# CH32V407VET-R0.net
KiCad netlist of a schematic drawn in Altium Designer
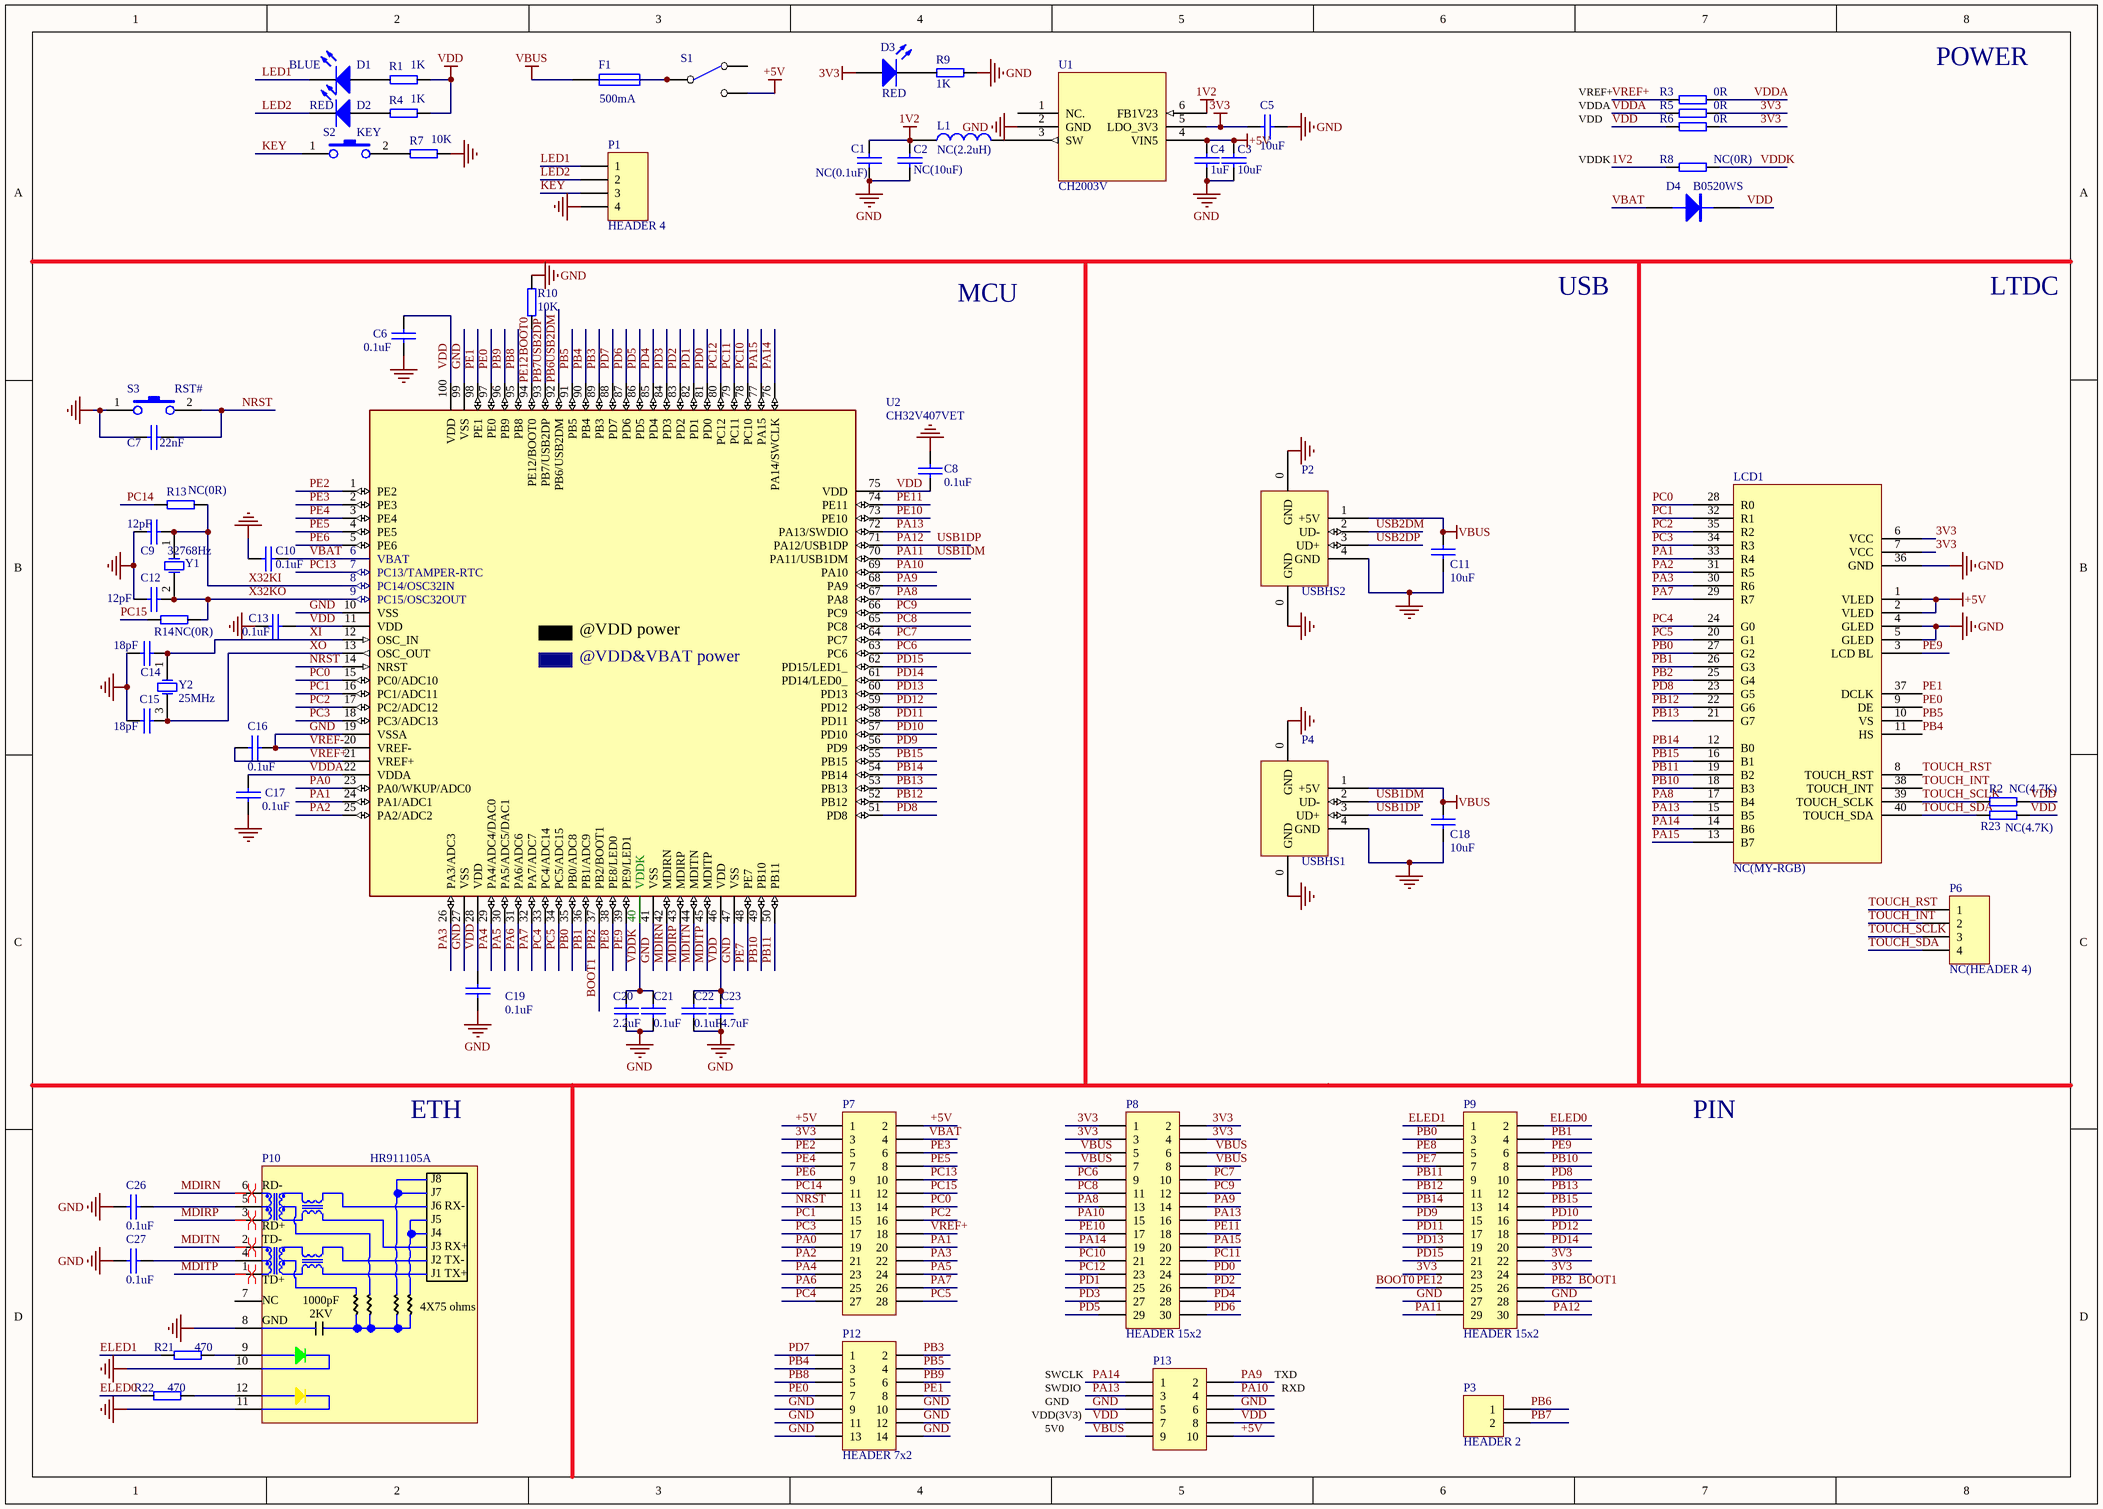
[diagram p0: CH32V407VET-R0.SchDoc]

(export (version "E")
  (design (tool "Eeschema 10.0.6"))
  (components
    (comp (ref "C1")
      (value "NC(0.1uF)")
      (footprint "0402_C")
      (description "Capacitor")
      (libsource (lib "") (part "CAP_2"))
    )
    (comp (ref "C2")
      (value "NC(10uF)")
      (footprint "0603_C")
      (description "Capacitor")
      (libsource (lib "*") (part "CAP"))
    )
    (comp (ref "C3")
      (value "10uF")
      (footprint "0603_C")
      (description "Capacitor")
      (libsource (lib "*") (part "CAP"))
    )
    (comp (ref "C4")
      (value "1uF")
      (footprint "0402_C")
      (description "Capacitor")
      (libsource (lib "") (part "CAP_2"))
    )
    (comp (ref "C5")
      (value "10uF")
      (footprint "0603_C")
      (description "Capacitor")
      (libsource (lib "*") (part "CAP"))
    )
    (comp (ref "C6")
      (value "0.1uF")
      (footprint "0402_C")
      (description "Capacitor")
      (libsource (lib "*") (part "CAP"))
    )
    (comp (ref "C7")
      (value "22nF")
      (footprint "0402_C")
      (description "Capacitor")
      (libsource (lib "") (part "CAP_1"))
    )
    (comp (ref "C8")
      (value "0.1uF")
      (footprint "0402_C")
      (description "Capacitor")
      (libsource (lib "*") (part "CAP"))
    )
    (comp (ref "C9")
      (value "12pF")
      (footprint "0402_C")
      (description "Capacitor")
      (libsource (lib "*") (part "CAP"))
    )
    (comp (ref "C10")
      (value "0.1uF")
      (footprint "0402_C")
      (description "Capacitor")
      (libsource (lib "*") (part "CAP"))
    )
    (comp (ref "C11")
      (value "10uF")
      (footprint "0603_C")
      (description "Capacitor")
      (libsource (lib "") (part "CAP_1"))
    )
    (comp (ref "C12")
      (value "12pF")
      (footprint "0402_C")
      (description "Capacitor")
      (libsource (lib "*") (part "CAP"))
    )
    (comp (ref "C13")
      (value "0.1uF")
      (footprint "0402_C")
      (description "Capacitor")
      (libsource (lib "*") (part "CAP"))
    )
    (comp (ref "C14")
      (value "18pF")
      (footprint "0402_C")
      (description "Capacitor")
      (libsource (lib "*") (part "CAP"))
    )
    (comp (ref "C15")
      (value "18pF")
      (footprint "0402_C")
      (description "Capacitor")
      (libsource (lib "*") (part "CAP"))
    )
    (comp (ref "C16")
      (value "0.1uF")
      (footprint "0402_C")
      (description "Capacitor")
      (libsource (lib "*") (part "CAP"))
    )
    (comp (ref "C17")
      (value "0.1uF")
      (footprint "0402_C")
      (description "Capacitor")
      (libsource (lib "*") (part "CAP"))
    )
    (comp (ref "C18")
      (value "10uF")
      (footprint "0603_C")
      (description "Capacitor")
      (libsource (lib "") (part "CAP_1"))
    )
    (comp (ref "C19")
      (value "0.1uF")
      (footprint "0402_C")
      (description "Capacitor")
      (libsource (lib "*") (part "CAP"))
    )
    (comp (ref "C20")
      (value "2.2uF")
      (footprint "0402_C")
      (description "Capacitor")
      (libsource (lib "*") (part "CAP"))
    )
    (comp (ref "C21")
      (value "0.1uF")
      (footprint "0402_C")
      (description "Capacitor")
      (libsource (lib "*") (part "CAP"))
    )
    (comp (ref "C22")
      (value "0.1uF")
      (footprint "0402_C")
      (description "Capacitor")
      (libsource (lib "*") (part "CAP"))
    )
    (comp (ref "C23")
      (value "4.7uF")
      (footprint "0402_C")
      (description "Capacitor")
      (libsource (lib "*") (part "CAP"))
    )
    (comp (ref "C26")
      (value "0.1uF")
      (footprint "0402_C")
      (description "Capacitor")
      (libsource (lib "wch_sch_others") (part "CAP"))
    )
    (comp (ref "C27")
      (value "0.1uF")
      (footprint "0402_C")
      (description "Capacitor")
      (libsource (lib "wch_sch_others") (part "CAP"))
    )
    (comp (ref "D1")
      (value "BLUE")
      (footprint "0603+")
      (description "Typical INFRARED GaAs LED")
      (fields (field (name "PUBLISHER") "Altium Limited"))
      (libsource (lib "*") (part "LED0"))
    )
    (comp (ref "D2")
      (value "RED")
      (footprint "0603+")
      (description "Typical INFRARED GaAs LED")
      (fields (field (name "PUBLISHER") "Altium Limited"))
      (libsource (lib "*") (part "LED0"))
    )
    (comp (ref "D3")
      (value "RED")
      (footprint "0603+")
      (description "Typical INFRARED GaAs LED")
      (fields (field (name "PUBLISHER") "Altium Limited"))
      (libsource (lib "*") (part "LED0"))
    )
    (comp (ref "D4")
      (value "B0520WS")
      (footprint "SOD-323")
      (description "Diode")
      (libsource (lib "*") (part "DIODE"))
    )
    (comp (ref "F1")
      (value "500mA")
      (footprint "0603")
      (description "Fuse")
      (libsource (lib "wch_sch_others") (part "FUSE1"))
    )
    (comp (ref "L1") (value "NC(2.2uH)") (footprint "CD32") (libsource (lib "*") (part "INDUCTOR")))
    (comp (ref "LCD1")
      (value "NC(MY-RGB)")
      (footprint "FPC40P-0.5-FK750M3")
      (libsource (lib "MY-显示") (part "MY-RGB"))
    )
    (comp (ref "P1")
      (value "HEADER 4")
      (footprint "SIP4-2.54mm")
      (description "Header, 4-Pin")
      (libsource (lib "wch_sch_others") (part "HEADER 4"))
    )
    (comp (ref "P2")
      (value "USBHS2")
      (footprint "USBAF")
      (description "USB Port")
      (libsource (lib "*") (part "USB"))
    )
    (comp (ref "P3")
      (value "HEADER 2")
      (footprint "MYPCB:SIP2-2.54mm")
      (description "Header, 2-Pin")
      (libsource (lib "wch_sch_others") (part "HEADER 2"))
    )
    (comp (ref "P4")
      (value "USBHS1")
      (footprint "USBAF")
      (description "USB Port")
      (libsource (lib "*") (part "USB"))
    )
    (comp (ref "P6")
      (value "NC(HEADER 4)")
      (footprint "SIP4-2.54mm")
      (description "Header, 4-Pin")
      (libsource (lib "wch_sch_others") (part "HEADER 4"))
    )
    (comp (ref "P7")
      (value "HEADER 14x2")
      (footprint "MYPCB:IDC28-2.54MM")
      (description "Header, 14-Pin, Dual row")
      (libsource (lib "wch_sch_others") (part "HEADER 14x2"))
    )
    (comp (ref "P8")
      (value "HEADER 15x2")
      (footprint "MYPCB:IDC30-2.54MM")
      (description "Header, 15-Pin, Dual row")
      (libsource (lib "wch_sch_others") (part "HEADER 15x2"))
    )
    (comp (ref "P9")
      (value "HEADER 15x2")
      (footprint "MYPCB:IDC30-2.54MM")
      (description "Header, 15-Pin, Dual row")
      (libsource (lib "wch_sch_others") (part "HEADER 15x2"))
    )
    (comp (ref "P10") (value "HR911105A") (footprint "HR911105A") (libsource (lib "*") (part "HR911105A")))
    (comp (ref "P12")
      (value "HEADER 7x2")
      (footprint "MYPCB:IDC14-2.54mm")
      (description "Header, 7-Pin, Dual row")
      (libsource (lib "wch_sch_others") (part "HEADER 7x2"))
    )
    (comp (ref "P13")
      (value "LINK")
      (footprint "IDC10-2.54mm")
      (description "Header, 5-Pin, Dual row, Right Angle")
      (fields (field (name "PUBLISHER") "Altium Limited"))
      (libsource (lib "Miscellaneous Connectors") (part "Header 5X2H"))
    )
    (comp (ref "R1") (value "1K") (footprint "0402") (libsource (lib "wch_sch_others") (part "RES")))
    (comp (ref "R2") (value "NC(4.7K)") (footprint "0402") (libsource (lib "wch_sch_others") (part "RES")))
    (comp (ref "R3") (value "0R") (footprint "0402") (libsource (lib "*") (part "R")))
    (comp (ref "R4") (value "1K") (footprint "0402") (libsource (lib "wch_sch_others") (part "RES")))
    (comp (ref "R5") (value "0R") (footprint "0402") (libsource (lib "*") (part "R")))
    (comp (ref "R6") (value "0R") (footprint "0402") (libsource (lib "*") (part "R")))
    (comp (ref "R7") (value "10K") (footprint "0402") (libsource (lib "wch_sch_others") (part "RES")))
    (comp (ref "R8") (value "NC(0R)") (footprint "0402") (libsource (lib "*") (part "R")))
    (comp (ref "R9") (value "1K") (footprint "0402") (libsource (lib "wch_sch_others") (part "RES")))
    (comp (ref "R10") (value "10K") (footprint "0402") (libsource (lib "wch_sch_others") (part "RES")))
    (comp (ref "R13") (value "NC(0R)") (footprint "0402") (libsource (lib "wch_sch_others") (part "RES")))
    (comp (ref "R14") (value "NC(0R)") (footprint "0402") (libsource (lib "wch_sch_others") (part "RES")))
    (comp (ref "R21") (value "470") (footprint "0402") (libsource (lib "wch_sch_others") (part "RES")))
    (comp (ref "R22") (value "470") (footprint "0402") (libsource (lib "wch_sch_others") (part "RES")))
    (comp (ref "R23") (value "NC(4.7K)") (footprint "0402") (libsource (lib "wch_sch_others") (part "RES")))
    (comp (ref "S1") (value "SW SPDT") (footprint "SW1") (libsource (lib "*") (part "SW SPDT")))
    (comp (ref "S2")
      (value "KEY")
      (footprint "SMD_6.1x3.65x2.5mm-KEY")
      (libsource (lib "wch_sch_others") (part "KEY1"))
    )
    (comp (ref "S3")
      (value "RST#")
      (footprint "SMD_6.1x3.65x2.5mm-KEY")
      (libsource (lib "wch_sch_others") (part "KEY1"))
    )
    (comp (ref "U1")
      (value "CH2003V")
      (footprint "SOT-23-6")
      (description "Step-Down DC-DC Converter, 5V input, 1.23V * 800mA output, with LDO 3.3V * 200mA")
      (libsource (lib "CHXXX") (part "CH2003V"))
    )
    (comp (ref "U2")
      (value "CH32V407VET")
      (footprint "LQFP100")
      (description "RISC-V FPU HD-MCU, 175MHz, USB_480M, 100M Ethernet & Phy, CAN, DVP, ADC, DAC")
      (libsource (lib "CHXXX") (part "CH32V407VET"))
    )
    (comp (ref "Y1")
      (value "32768Hz")
      (footprint "FC-135")
      (description "Crystal Oscillator")
      (fields (field (name "PUBLISHER") "Altium Limited"))
      (libsource (lib "*") (part "XTAL"))
    )
    (comp (ref "Y2")
      (value "25MHz")
      (footprint "XT3225")
      (description "Crystal Oscillator")
      (fields (field (name "PUBLISHER") "Altium Limited"))
      (libsource (lib "") (part "XTAL_1"))
    )
  )
  (nets
    (net (code "1") (name "+5V") (class "Default")
      (node (ref "C3") (pin "2") (pinfunction "2_2") (pintype "passive"))
      (node (ref "C4") (pin "2") (pinfunction "2_2") (pintype "passive"))
      (node (ref "LCD1") (pin "1") (pinfunction "VLED_1") (pintype "passive"))
      (node (ref "LCD1") (pin "2") (pinfunction "VLED_2") (pintype "passive"))
      (node (ref "P13") (pin "10") (pinfunction "10_10") (pintype "passive"))
      (node (ref "P7") (pin "1") (pinfunction "1_1") (pintype "passive"))
      (node (ref "P7") (pin "2") (pinfunction "2_2") (pintype "passive"))
      (node (ref "S1") (pin "2") (pinfunction "NC_2") (pintype "passive"))
      (node (ref "U1") (pin "4") (pinfunction "VIN5_4") (pintype "power_in"))
    )
    (net (code "3") (name "/BOOT0") (class "Default")
      (node (ref "P9") (pin "25") (pinfunction "25_25") (pintype "passive"))
      (node (ref "R10") (pin "2") (pintype "passive"))
      (node (ref "U2") (pin "94") (pinfunction "PE12/BOOT0_94") (pintype "bidirectional"))
    )
    (net (code "4") (name "/BOOT1") (class "Default")
      (node (ref "LCD1") (pin "25") (pinfunction "G4_25") (pintype "passive"))
      (node (ref "P9") (pin "26") (pinfunction "26_26") (pintype "passive"))
      (node (ref "U2") (pin "37") (pinfunction "PB2/BOOT1_37") (pintype "bidirectional"))
    )
    (net (code "5") (name "/ELED0") (class "Default")
      (node (ref "P9") (pin "2") (pinfunction "2_2") (pintype "passive"))
      (node (ref "R22") (pin "1") (pintype "passive"))
    )
    (net (code "6") (name "/ELED1") (class "Default")
      (node (ref "P9") (pin "1") (pinfunction "1_1") (pintype "passive"))
      (node (ref "R21") (pin "1") (pintype "passive"))
    )
    (net (code "7") (name "/KEY") (class "Default")
      (node (ref "P1") (pin "3") (pinfunction "3_3") (pintype "passive"))
      (node (ref "S2") (pin "1") (pinfunction "1_1") (pintype "passive"))
    )
    (net (code "8") (name "/LED1") (class "Default")
      (node (ref "D1") (pin "2") (pinfunction "K_2") (pintype "passive"))
      (node (ref "P1") (pin "1") (pinfunction "1_1") (pintype "passive"))
    )
    (net (code "9") (name "/LED2") (class "Default")
      (node (ref "D2") (pin "2") (pinfunction "K_2") (pintype "passive"))
      (node (ref "P1") (pin "2") (pinfunction "2_2") (pintype "passive"))
    )
    (net (code "10") (name "/MDIRN") (class "Default")
      (node (ref "P10") (pin "6") (pintype "passive"))
      (node (ref "U2") (pin "42") (pinfunction "MDIRN_42") (pintype "bidirectional"))
    )
    (net (code "11") (name "/MDIRP") (class "Default")
      (node (ref "P10") (pin "3") (pintype "passive"))
      (node (ref "U2") (pin "43") (pinfunction "MDIRP_43") (pintype "bidirectional"))
    )
    (net (code "12") (name "/MDITN") (class "Default")
      (node (ref "P10") (pin "2") (pintype "passive"))
      (node (ref "U2") (pin "44") (pinfunction "MDITN_44") (pintype "bidirectional"))
    )
    (net (code "13") (name "/MDITP") (class "Default")
      (node (ref "P10") (pin "1") (pintype "passive"))
      (node (ref "U2") (pin "45") (pinfunction "MDITP_45") (pintype "bidirectional"))
    )
    (net (code "14") (name "/NRST") (class "Default")
      (node (ref "C7") (pin "2") (pinfunction "2_2") (pintype "passive"))
      (node (ref "P7") (pin "13") (pinfunction "13_13") (pintype "passive"))
      (node (ref "S3") (pin "2") (pinfunction "2_2") (pintype "passive"))
      (node (ref "U2") (pin "14") (pinfunction "NRST_14") (pintype "input"))
    )
    (net (code "15") (name "/PA0") (class "Default")
      (node (ref "P7") (pin "19") (pinfunction "19_19") (pintype "passive"))
      (node (ref "U2") (pin "23") (pinfunction "PA0/WKUP/ADC0_23") (pintype "bidirectional"))
    )
    (net (code "16") (name "/PA1") (class "Default")
      (node (ref "LCD1") (pin "33") (pinfunction "R4_33") (pintype "passive"))
      (node (ref "P7") (pin "20") (pinfunction "20_20") (pintype "passive"))
      (node (ref "U2") (pin "24") (pinfunction "PA1/ADC1_24") (pintype "bidirectional"))
    )
    (net (code "17") (name "/PA2") (class "Default")
      (node (ref "LCD1") (pin "31") (pinfunction "R5_31") (pintype "passive"))
      (node (ref "P7") (pin "21") (pinfunction "21_21") (pintype "passive"))
      (node (ref "U2") (pin "25") (pinfunction "PA2/ADC2_25") (pintype "bidirectional"))
    )
    (net (code "18") (name "/PA3") (class "Default")
      (node (ref "LCD1") (pin "30") (pinfunction "R6_30") (pintype "passive"))
      (node (ref "P7") (pin "22") (pinfunction "22_22") (pintype "passive"))
      (node (ref "U2") (pin "26") (pinfunction "PA3/ADC3_26") (pintype "bidirectional"))
    )
    (net (code "19") (name "/PA4") (class "Default")
      (node (ref "P7") (pin "23") (pinfunction "23_23") (pintype "passive"))
      (node (ref "U2") (pin "29") (pinfunction "PA4/ADC4/DAC0_29") (pintype "bidirectional"))
    )
    (net (code "20") (name "/PA5") (class "Default")
      (node (ref "P7") (pin "24") (pinfunction "24_24") (pintype "passive"))
      (node (ref "U2") (pin "30") (pinfunction "PA5/ADC5/DAC1_30") (pintype "bidirectional"))
    )
    (net (code "21") (name "/PA6") (class "Default")
      (node (ref "P7") (pin "25") (pinfunction "25_25") (pintype "passive"))
      (node (ref "U2") (pin "31") (pinfunction "PA6/ADC6_31") (pintype "bidirectional"))
    )
    (net (code "22") (name "/PA7") (class "Default")
      (node (ref "LCD1") (pin "29") (pinfunction "R7_29") (pintype "passive"))
      (node (ref "P7") (pin "26") (pinfunction "26_26") (pintype "passive"))
      (node (ref "U2") (pin "32") (pinfunction "PA7/ADC7_32") (pintype "bidirectional"))
    )
    (net (code "23") (name "/PA8") (class "Default")
      (node (ref "LCD1") (pin "17") (pinfunction "B4_17") (pintype "passive"))
      (node (ref "P8") (pin "13") (pinfunction "13_13") (pintype "passive"))
      (node (ref "U2") (pin "67") (pinfunction "PA8_67") (pintype "bidirectional"))
    )
    (net (code "24") (name "/PA9") (class "Default")
      (node (ref "P13") (pin "2") (pinfunction "2_2") (pintype "passive"))
      (node (ref "P8") (pin "14") (pinfunction "14_14") (pintype "passive"))
      (node (ref "U2") (pin "68") (pinfunction "PA9_68") (pintype "bidirectional"))
    )
    (net (code "25") (name "/PA10") (class "Default")
      (node (ref "P13") (pin "4") (pinfunction "4_4") (pintype "passive"))
      (node (ref "P8") (pin "15") (pinfunction "15_15") (pintype "passive"))
      (node (ref "U2") (pin "69") (pinfunction "PA10_69") (pintype "bidirectional"))
    )
    (net (code "26") (name "/PA11") (class "Default")
      (node (ref "P4") (pin "2") (pinfunction "UD-_2") (pintype "bidirectional"))
      (node (ref "P9") (pin "29") (pinfunction "29_29") (pintype "passive"))
      (node (ref "U2") (pin "70") (pinfunction "PA11/USB1DM_70") (pintype "bidirectional"))
    )
    (net (code "27") (name "/PA12") (class "Default")
      (node (ref "P4") (pin "3") (pinfunction "UD+_3") (pintype "bidirectional"))
      (node (ref "P9") (pin "30") (pinfunction "30_30") (pintype "passive"))
      (node (ref "U2") (pin "71") (pinfunction "PA12/USB1DP_71") (pintype "bidirectional"))
    )
    (net (code "28") (name "/PA13") (class "Default")
      (node (ref "LCD1") (pin "15") (pinfunction "B5_15") (pintype "passive"))
      (node (ref "P13") (pin "3") (pinfunction "3_3") (pintype "passive"))
      (node (ref "P8") (pin "16") (pinfunction "16_16") (pintype "passive"))
      (node (ref "U2") (pin "72") (pinfunction "PA13/SWDIO_72") (pintype "bidirectional"))
    )
    (net (code "29") (name "/PA14") (class "Default")
      (node (ref "LCD1") (pin "14") (pinfunction "B6_14") (pintype "passive"))
      (node (ref "P13") (pin "1") (pinfunction "1_1") (pintype "passive"))
      (node (ref "P8") (pin "19") (pinfunction "19_19") (pintype "passive"))
      (node (ref "U2") (pin "76") (pinfunction "PA14/SWCLK_76") (pintype "bidirectional"))
    )
    (net (code "30") (name "/PA15") (class "Default")
      (node (ref "LCD1") (pin "13") (pinfunction "B7_13") (pintype "passive"))
      (node (ref "P8") (pin "20") (pinfunction "20_20") (pintype "passive"))
      (node (ref "U2") (pin "77") (pinfunction "PA15_77") (pintype "bidirectional"))
    )
    (net (code "31") (name "/PB0") (class "Default")
      (node (ref "LCD1") (pin "27") (pinfunction "G2_27") (pintype "passive"))
      (node (ref "P9") (pin "3") (pinfunction "3_3") (pintype "passive"))
      (node (ref "U2") (pin "35") (pinfunction "PB0/ADC8_35") (pintype "bidirectional"))
    )
    (net (code "32") (name "/PB1") (class "Default")
      (node (ref "LCD1") (pin "26") (pinfunction "G3_26") (pintype "passive"))
      (node (ref "P9") (pin "4") (pinfunction "4_4") (pintype "passive"))
      (node (ref "U2") (pin "36") (pinfunction "PB1/ADC9_36") (pintype "bidirectional"))
    )
    (net (code "33") (name "/PB3") (class "Default")
      (node (ref "P12") (pin "2") (pinfunction "2_2") (pintype "passive"))
      (node (ref "U2") (pin "89") (pinfunction "PB3_89") (pintype "bidirectional"))
    )
    (net (code "34") (name "/PB4") (class "Default")
      (node (ref "LCD1") (pin "11") (pinfunction "HS_11") (pintype "passive"))
      (node (ref "P12") (pin "3") (pinfunction "3_3") (pintype "passive"))
      (node (ref "U2") (pin "90") (pinfunction "PB4_90") (pintype "bidirectional"))
    )
    (net (code "35") (name "/PB5") (class "Default")
      (node (ref "LCD1") (pin "10") (pinfunction "VS_10") (pintype "passive"))
      (node (ref "P12") (pin "4") (pinfunction "4_4") (pintype "passive"))
      (node (ref "U2") (pin "91") (pinfunction "PB5_91") (pintype "bidirectional"))
    )
    (net (code "36") (name "/PB6") (class "Default")
      (node (ref "P2") (pin "2") (pinfunction "UD-_2") (pintype "bidirectional"))
      (node (ref "P3") (pin "1") (pinfunction "1_1") (pintype "passive"))
      (node (ref "U2") (pin "92") (pinfunction "PB6/USB2DM_92") (pintype "bidirectional"))
    )
    (net (code "37") (name "/PB7") (class "Default")
      (node (ref "P2") (pin "3") (pinfunction "UD+_3") (pintype "bidirectional"))
      (node (ref "P3") (pin "2") (pinfunction "2_2") (pintype "passive"))
      (node (ref "U2") (pin "93") (pinfunction "PB7/USB2DP_93") (pintype "bidirectional"))
    )
    (net (code "38") (name "/PB8") (class "Default")
      (node (ref "P12") (pin "5") (pinfunction "5_5") (pintype "passive"))
      (node (ref "U2") (pin "95") (pinfunction "PB8_95") (pintype "bidirectional"))
    )
    (net (code "39") (name "/PB9") (class "Default")
      (node (ref "P12") (pin "6") (pinfunction "6_6") (pintype "passive"))
      (node (ref "U2") (pin "96") (pinfunction "PB9_96") (pintype "bidirectional"))
    )
    (net (code "40") (name "/PB10") (class "Default")
      (node (ref "LCD1") (pin "18") (pinfunction "B3_18") (pintype "passive"))
      (node (ref "P9") (pin "8") (pinfunction "8_8") (pintype "passive"))
      (node (ref "U2") (pin "49") (pinfunction "PB10_49") (pintype "bidirectional"))
    )
    (net (code "41") (name "/PB11") (class "Default")
      (node (ref "LCD1") (pin "19") (pinfunction "B2_19") (pintype "passive"))
      (node (ref "P9") (pin "9") (pinfunction "9_9") (pintype "passive"))
      (node (ref "U2") (pin "50") (pinfunction "PB11_50") (pintype "bidirectional"))
    )
    (net (code "42") (name "/PB12") (class "Default")
      (node (ref "LCD1") (pin "22") (pinfunction "G6_22") (pintype "passive"))
      (node (ref "P9") (pin "11") (pinfunction "11_11") (pintype "passive"))
      (node (ref "U2") (pin "52") (pinfunction "PB12_52") (pintype "bidirectional"))
    )
    (net (code "43") (name "/PB13") (class "Default")
      (node (ref "LCD1") (pin "21") (pinfunction "G7_21") (pintype "passive"))
      (node (ref "P9") (pin "12") (pinfunction "12_12") (pintype "passive"))
      (node (ref "U2") (pin "53") (pinfunction "PB13_53") (pintype "bidirectional"))
    )
    (net (code "44") (name "/PB14") (class "Default")
      (node (ref "LCD1") (pin "12") (pinfunction "B0_12") (pintype "passive"))
      (node (ref "P9") (pin "13") (pinfunction "13_13") (pintype "passive"))
      (node (ref "U2") (pin "54") (pinfunction "PB14_54") (pintype "bidirectional"))
    )
    (net (code "45") (name "/PB15") (class "Default")
      (node (ref "LCD1") (pin "16") (pinfunction "B1_16") (pintype "passive"))
      (node (ref "P9") (pin "14") (pinfunction "14_14") (pintype "passive"))
      (node (ref "U2") (pin "55") (pinfunction "PB15_55") (pintype "bidirectional"))
    )
    (net (code "46") (name "/PC0") (class "Default")
      (node (ref "LCD1") (pin "28") (pinfunction "R0_28") (pintype "passive"))
      (node (ref "P7") (pin "14") (pinfunction "14_14") (pintype "passive"))
      (node (ref "U2") (pin "15") (pinfunction "PC0/ADC10_15") (pintype "bidirectional"))
    )
    (net (code "47") (name "/PC1") (class "Default")
      (node (ref "LCD1") (pin "32") (pinfunction "R1_32") (pintype "passive"))
      (node (ref "P7") (pin "15") (pinfunction "15_15") (pintype "passive"))
      (node (ref "U2") (pin "16") (pinfunction "PC1/ADC11_16") (pintype "bidirectional"))
    )
    (net (code "48") (name "/PC2") (class "Default")
      (node (ref "LCD1") (pin "35") (pinfunction "R2_35") (pintype "passive"))
      (node (ref "P7") (pin "16") (pinfunction "16_16") (pintype "passive"))
      (node (ref "U2") (pin "17") (pinfunction "PC2/ADC12_17") (pintype "bidirectional"))
    )
    (net (code "49") (name "/PC3") (class "Default")
      (node (ref "LCD1") (pin "34") (pinfunction "R3_34") (pintype "passive"))
      (node (ref "P7") (pin "17") (pinfunction "17_17") (pintype "passive"))
      (node (ref "U2") (pin "18") (pinfunction "PC3/ADC13_18") (pintype "bidirectional"))
    )
    (net (code "50") (name "/PC4") (class "Default")
      (node (ref "LCD1") (pin "24") (pinfunction "G0_24") (pintype "passive"))
      (node (ref "P7") (pin "27") (pinfunction "27_27") (pintype "passive"))
      (node (ref "U2") (pin "33") (pinfunction "PC4/ADC14_33") (pintype "bidirectional"))
    )
    (net (code "51") (name "/PC5") (class "Default")
      (node (ref "LCD1") (pin "20") (pinfunction "G1_20") (pintype "passive"))
      (node (ref "P7") (pin "28") (pinfunction "28_28") (pintype "passive"))
      (node (ref "U2") (pin "34") (pinfunction "PC5/ADC15_34") (pintype "bidirectional"))
    )
    (net (code "52") (name "/PC6") (class "Default")
      (node (ref "P8") (pin "9") (pinfunction "9_9") (pintype "passive"))
      (node (ref "U2") (pin "63") (pinfunction "PC6_63") (pintype "bidirectional"))
    )
    (net (code "53") (name "/PC7") (class "Default")
      (node (ref "P8") (pin "10") (pinfunction "10_10") (pintype "passive"))
      (node (ref "U2") (pin "64") (pinfunction "PC7_64") (pintype "bidirectional"))
    )
    (net (code "54") (name "/PC8") (class "Default")
      (node (ref "P8") (pin "11") (pinfunction "11_11") (pintype "passive"))
      (node (ref "U2") (pin "65") (pinfunction "PC8_65") (pintype "bidirectional"))
    )
    (net (code "55") (name "/PC9") (class "Default")
      (node (ref "P8") (pin "12") (pinfunction "12_12") (pintype "passive"))
      (node (ref "U2") (pin "66") (pinfunction "PC9_66") (pintype "bidirectional"))
    )
    (net (code "56") (name "/PC10") (class "Default")
      (node (ref "P8") (pin "21") (pinfunction "21_21") (pintype "passive"))
      (node (ref "U2") (pin "78") (pinfunction "PC10_78") (pintype "bidirectional"))
    )
    (net (code "57") (name "/PC11") (class "Default")
      (node (ref "P8") (pin "22") (pinfunction "22_22") (pintype "passive"))
      (node (ref "U2") (pin "79") (pinfunction "PC11_79") (pintype "bidirectional"))
    )
    (net (code "58") (name "/PC12") (class "Default")
      (node (ref "P8") (pin "23") (pinfunction "23_23") (pintype "passive"))
      (node (ref "U2") (pin "80") (pinfunction "PC12_80") (pintype "bidirectional"))
    )
    (net (code "59") (name "/PC13") (class "Default")
      (node (ref "P7") (pin "10") (pinfunction "10_10") (pintype "passive"))
      (node (ref "U2") (pin "7") (pinfunction "PC13/TAMPER-RTC_7") (pintype "bidirectional"))
    )
    (net (code "60") (name "/PC14") (class "Default")
      (node (ref "P7") (pin "11") (pinfunction "11_11") (pintype "passive"))
      (node (ref "R13") (pin "1") (pintype "passive"))
    )
    (net (code "61") (name "/PC15") (class "Default")
      (node (ref "P7") (pin "12") (pinfunction "12_12") (pintype "passive"))
      (node (ref "R14") (pin "1") (pintype "passive"))
    )
    (net (code "62") (name "/PD0") (class "Default")
      (node (ref "P8") (pin "24") (pinfunction "24_24") (pintype "passive"))
      (node (ref "U2") (pin "81") (pinfunction "PD0_81") (pintype "bidirectional"))
    )
    (net (code "63") (name "/PD1") (class "Default")
      (node (ref "P8") (pin "25") (pinfunction "25_25") (pintype "passive"))
      (node (ref "U2") (pin "82") (pinfunction "PD1_82") (pintype "bidirectional"))
    )
    (net (code "64") (name "/PD2") (class "Default")
      (node (ref "P8") (pin "26") (pinfunction "26_26") (pintype "passive"))
      (node (ref "U2") (pin "83") (pinfunction "PD2_83") (pintype "bidirectional"))
    )
    (net (code "65") (name "/PD3") (class "Default")
      (node (ref "P8") (pin "27") (pinfunction "27_27") (pintype "passive"))
      (node (ref "U2") (pin "84") (pinfunction "PD3_84") (pintype "bidirectional"))
    )
    (net (code "66") (name "/PD4") (class "Default")
      (node (ref "P8") (pin "28") (pinfunction "28_28") (pintype "passive"))
      (node (ref "U2") (pin "85") (pinfunction "PD4_85") (pintype "bidirectional"))
    )
    (net (code "67") (name "/PD5") (class "Default")
      (node (ref "P8") (pin "29") (pinfunction "29_29") (pintype "passive"))
      (node (ref "U2") (pin "86") (pinfunction "PD5_86") (pintype "bidirectional"))
    )
    (net (code "68") (name "/PD6") (class "Default")
      (node (ref "P8") (pin "30") (pinfunction "30_30") (pintype "passive"))
      (node (ref "U2") (pin "87") (pinfunction "PD6_87") (pintype "bidirectional"))
    )
    (net (code "69") (name "/PD7") (class "Default")
      (node (ref "P12") (pin "1") (pinfunction "1_1") (pintype "passive"))
      (node (ref "U2") (pin "88") (pinfunction "PD7_88") (pintype "bidirectional"))
    )
    (net (code "70") (name "/PD8") (class "Default")
      (node (ref "LCD1") (pin "23") (pinfunction "G5_23") (pintype "passive"))
      (node (ref "P9") (pin "10") (pinfunction "10_10") (pintype "passive"))
      (node (ref "U2") (pin "51") (pinfunction "PD8_51") (pintype "bidirectional"))
    )
    (net (code "71") (name "/PD9") (class "Default")
      (node (ref "P9") (pin "15") (pinfunction "15_15") (pintype "passive"))
      (node (ref "U2") (pin "56") (pinfunction "PD9_56") (pintype "bidirectional"))
    )
    (net (code "72") (name "/PD10") (class "Default")
      (node (ref "P9") (pin "16") (pinfunction "16_16") (pintype "passive"))
      (node (ref "U2") (pin "57") (pinfunction "PD10_57") (pintype "bidirectional"))
    )
    (net (code "73") (name "/PD11") (class "Default")
      (node (ref "P9") (pin "17") (pinfunction "17_17") (pintype "passive"))
      (node (ref "U2") (pin "58") (pinfunction "PD11_58") (pintype "bidirectional"))
    )
    (net (code "74") (name "/PD12") (class "Default")
      (node (ref "P9") (pin "18") (pinfunction "18_18") (pintype "passive"))
      (node (ref "U2") (pin "59") (pinfunction "PD12_59") (pintype "bidirectional"))
    )
    (net (code "75") (name "/PD13") (class "Default")
      (node (ref "P9") (pin "19") (pinfunction "19_19") (pintype "passive"))
      (node (ref "U2") (pin "60") (pinfunction "PD13_60") (pintype "bidirectional"))
    )
    (net (code "76") (name "/PD14") (class "Default")
      (node (ref "P9") (pin "20") (pinfunction "20_20") (pintype "passive"))
      (node (ref "U2") (pin "61") (pinfunction "PD14/LED0__61") (pintype "bidirectional"))
    )
    (net (code "77") (name "/PD15") (class "Default")
      (node (ref "P9") (pin "21") (pinfunction "21_21") (pintype "passive"))
      (node (ref "U2") (pin "62") (pinfunction "PD15/LED1__62") (pintype "bidirectional"))
    )
    (net (code "78") (name "/PE0") (class "Default")
      (node (ref "LCD1") (pin "9") (pinfunction "DE_9") (pintype "passive"))
      (node (ref "P12") (pin "7") (pinfunction "7_7") (pintype "passive"))
      (node (ref "U2") (pin "97") (pinfunction "PE0_97") (pintype "bidirectional"))
    )
    (net (code "79") (name "/PE1") (class "Default")
      (node (ref "LCD1") (pin "37") (pinfunction "DCLK_37") (pintype "passive"))
      (node (ref "P12") (pin "8") (pinfunction "8_8") (pintype "passive"))
      (node (ref "U2") (pin "98") (pinfunction "PE1_98") (pintype "bidirectional"))
    )
    (net (code "80") (name "/PE2") (class "Default")
      (node (ref "P7") (pin "5") (pinfunction "5_5") (pintype "passive"))
      (node (ref "U2") (pin "1") (pinfunction "PE2_1") (pintype "bidirectional"))
    )
    (net (code "81") (name "/PE3") (class "Default")
      (node (ref "P7") (pin "6") (pinfunction "6_6") (pintype "passive"))
      (node (ref "U2") (pin "2") (pinfunction "PE3_2") (pintype "bidirectional"))
    )
    (net (code "82") (name "/PE4") (class "Default")
      (node (ref "P7") (pin "7") (pinfunction "7_7") (pintype "passive"))
      (node (ref "U2") (pin "3") (pinfunction "PE4_3") (pintype "bidirectional"))
    )
    (net (code "83") (name "/PE5") (class "Default")
      (node (ref "P7") (pin "8") (pinfunction "8_8") (pintype "passive"))
      (node (ref "U2") (pin "4") (pinfunction "PE5_4") (pintype "bidirectional"))
    )
    (net (code "84") (name "/PE6") (class "Default")
      (node (ref "P7") (pin "9") (pinfunction "9_9") (pintype "passive"))
      (node (ref "U2") (pin "5") (pinfunction "PE6_5") (pintype "bidirectional"))
    )
    (net (code "85") (name "/PE7") (class "Default")
      (node (ref "P9") (pin "7") (pinfunction "7_7") (pintype "passive"))
      (node (ref "U2") (pin "48") (pinfunction "PE7_48") (pintype "bidirectional"))
    )
    (net (code "86") (name "/PE8") (class "Default")
      (node (ref "P9") (pin "5") (pinfunction "5_5") (pintype "passive"))
      (node (ref "U2") (pin "38") (pinfunction "PE8/LED0_38") (pintype "bidirectional"))
    )
    (net (code "87") (name "/PE9") (class "Default")
      (node (ref "LCD1") (pin "3") (pinfunction "LCD_BL_3") (pintype "passive"))
      (node (ref "P9") (pin "6") (pinfunction "6_6") (pintype "passive"))
      (node (ref "U2") (pin "39") (pinfunction "PE9/LED1_39") (pintype "bidirectional"))
    )
    (net (code "88") (name "/PE10") (class "Default")
      (node (ref "P8") (pin "17") (pinfunction "17_17") (pintype "passive"))
      (node (ref "U2") (pin "73") (pinfunction "PE10_73") (pintype "bidirectional"))
    )
    (net (code "89") (name "/PE11") (class "Default")
      (node (ref "P8") (pin "18") (pinfunction "18_18") (pintype "passive"))
      (node (ref "U2") (pin "74") (pinfunction "PE11_74") (pintype "bidirectional"))
    )
    (net (code "90") (name "/TOUCH_INT") (class "Default")
      (node (ref "LCD1") (pin "38") (pinfunction "TOUCH_INT_38") (pintype "passive"))
      (node (ref "P6") (pin "2") (pinfunction "2_2") (pintype "passive"))
    )
    (net (code "91") (name "/TOUCH_RST") (class "Default")
      (node (ref "LCD1") (pin "8") (pinfunction "TOUCH_RST_8") (pintype "passive"))
      (node (ref "P6") (pin "1") (pinfunction "1_1") (pintype "passive"))
    )
    (net (code "92") (name "/TOUCH_SCLK") (class "Default")
      (node (ref "LCD1") (pin "39") (pinfunction "TOUCH_SCLK_39") (pintype "passive"))
      (node (ref "P6") (pin "3") (pinfunction "3_3") (pintype "passive"))
      (node (ref "R2") (pin "2") (pintype "passive"))
    )
    (net (code "93") (name "/TOUCH_SDA") (class "Default")
      (node (ref "LCD1") (pin "40") (pinfunction "TOUCH_SDA_40") (pintype "passive"))
      (node (ref "P6") (pin "4") (pinfunction "4_4") (pintype "passive"))
      (node (ref "R23") (pin "2") (pintype "passive"))
    )
    (net (code "94") (name "/VBAT") (class "Default")
      (node (ref "C10") (pin "2") (pinfunction "2_2") (pintype "passive"))
      (node (ref "D4") (pin "1") (pinfunction "A_1") (pintype "passive"))
      (node (ref "P7") (pin "4") (pinfunction "4_4") (pintype "passive"))
      (node (ref "U2") (pin "6") (pinfunction "VBAT_6") (pintype "power_in"))
    )
    (net (code "95") (name "/VDDA") (class "Default")
      (node (ref "C17") (pin "1") (pinfunction "1_1") (pintype "passive"))
      (node (ref "R3") (pin "1") (pinfunction "1_1") (pintype "passive"))
      (node (ref "R5") (pin "2") (pinfunction "2_2") (pintype "passive"))
      (node (ref "U2") (pin "22") (pinfunction "VDDA_22") (pintype "power_in"))
    )
    (net (code "96") (name "/VDDK") (class "Default")
      (node (ref "C20") (pin "2") (pinfunction "2_2") (pintype "passive"))
      (node (ref "C21") (pin "2") (pinfunction "2_2") (pintype "passive"))
      (node (ref "R8") (pin "1") (pinfunction "1_1") (pintype "passive"))
      (node (ref "U2") (pin "40") (pinfunction "VDDK_40") (pintype "power_in"))
    )
    (net (code "97") (name "/VREF+") (class "Default")
      (node (ref "C16") (pin "1") (pinfunction "1_1") (pintype "passive"))
      (node (ref "P7") (pin "18") (pinfunction "18_18") (pintype "passive"))
      (node (ref "R3") (pin "2") (pinfunction "2_2") (pintype "passive"))
      (node (ref "U2") (pin "21") (pinfunction "VREF+_21") (pintype "power_in"))
    )
    (net (code "98") (name "/X32KI") (class "Default")
      (node (ref "C9") (pin "2") (pinfunction "2_2") (pintype "passive"))
      (node (ref "R13") (pin "2") (pintype "passive"))
      (node (ref "U2") (pin "8") (pinfunction "PC14/OSC32IN_8") (pintype "bidirectional"))
      (node (ref "Y1") (pin "1") (pinfunction "OSC1_1") (pintype "passive"))
    )
    (net (code "99") (name "/X32KO") (class "Default")
      (node (ref "C12") (pin "2") (pinfunction "2_2") (pintype "passive"))
      (node (ref "R14") (pin "2") (pintype "passive"))
      (node (ref "U2") (pin "9") (pinfunction "PC15/OSC32OUT_9") (pintype "bidirectional"))
      (node (ref "Y1") (pin "2") (pinfunction "OSC2_2") (pintype "passive"))
    )
    (net (code "100") (name "/XI") (class "Default")
      (node (ref "C14") (pin "2") (pinfunction "2_2") (pintype "passive"))
      (node (ref "U2") (pin "12") (pinfunction "OSC_IN_12") (pintype "input"))
      (node (ref "Y2") (pin "1") (pinfunction "OSC1_1") (pintype "passive"))
    )
    (net (code "101") (name "/XO") (class "Default")
      (node (ref "C15") (pin "2") (pinfunction "2_2") (pintype "passive"))
      (node (ref "U2") (pin "13") (pinfunction "OSC_OUT_13") (pintype "output"))
      (node (ref "Y2") (pin "3") (pinfunction "OSC2_3") (pintype "passive"))
    )
    (net (code "102") (name "1V2") (class "Default")
      (node (ref "C1") (pin "2") (pinfunction "2_2") (pintype "passive"))
      (node (ref "C2") (pin "2") (pinfunction "2_2") (pintype "passive"))
      (node (ref "L1") (pin "2") (pinfunction "2_2") (pintype "passive"))
      (node (ref "R8") (pin "2") (pinfunction "2_2") (pintype "passive"))
      (node (ref "U1") (pin "6") (pinfunction "FB1V23_6") (pintype "input"))
    )
    (net (code "103") (name "3V3") (class "Default")
      (node (ref "C5") (pin "2") (pinfunction "2_2") (pintype "passive"))
      (node (ref "D3") (pin "1") (pinfunction "A_1") (pintype "passive"))
      (node (ref "LCD1") (pin "6") (pinfunction "VCC_6") (pintype "passive"))
      (node (ref "LCD1") (pin "7") (pinfunction "VCC_7") (pintype "passive"))
      (node (ref "P7") (pin "3") (pinfunction "3_3") (pintype "passive"))
      (node (ref "P8") (pin "1") (pinfunction "1_1") (pintype "passive"))
      (node (ref "P8") (pin "2") (pinfunction "2_2") (pintype "passive"))
      (node (ref "P8") (pin "3") (pinfunction "3_3") (pintype "passive"))
      (node (ref "P8") (pin "4") (pinfunction "4_4") (pintype "passive"))
      (node (ref "P9") (pin "22") (pinfunction "22_22") (pintype "passive"))
      (node (ref "P9") (pin "23") (pinfunction "23_23") (pintype "passive"))
      (node (ref "P9") (pin "24") (pinfunction "24_24") (pintype "passive"))
      (node (ref "R5") (pin "1") (pinfunction "1_1") (pintype "passive"))
      (node (ref "R6") (pin "1") (pinfunction "1_1") (pintype "passive"))
      (node (ref "U1") (pin "5") (pinfunction "LDO_3V3_5") (pintype "power_in"))
    )
    (net (code "104") (name "GND") (class "Default")
      (node (ref "C1") (pin "1") (pinfunction "1_1") (pintype "passive"))
      (node (ref "C10") (pin "1") (pinfunction "1_1") (pintype "passive"))
      (node (ref "C11") (pin "2") (pinfunction "2_2") (pintype "passive"))
      (node (ref "C12") (pin "1") (pinfunction "1_1") (pintype "passive"))
      (node (ref "C13") (pin "2") (pinfunction "2_2") (pintype "passive"))
      (node (ref "C14") (pin "1") (pinfunction "1_1") (pintype "passive"))
      (node (ref "C15") (pin "1") (pinfunction "1_1") (pintype "passive"))
      (node (ref "C16") (pin "2") (pinfunction "2_2") (pintype "passive"))
      (node (ref "C17") (pin "2") (pinfunction "2_2") (pintype "passive"))
      (node (ref "C18") (pin "2") (pinfunction "2_2") (pintype "passive"))
      (node (ref "C19") (pin "1") (pinfunction "1_1") (pintype "passive"))
      (node (ref "C2") (pin "1") (pinfunction "1_1") (pintype "passive"))
      (node (ref "C20") (pin "1") (pinfunction "1_1") (pintype "passive"))
      (node (ref "C21") (pin "1") (pinfunction "1_1") (pintype "passive"))
      (node (ref "C22") (pin "1") (pinfunction "1_1") (pintype "passive"))
      (node (ref "C23") (pin "1") (pinfunction "1_1") (pintype "passive"))
      (node (ref "C26") (pin "1") (pinfunction "1_1") (pintype "passive"))
      (node (ref "C27") (pin "1") (pinfunction "1_1") (pintype "passive"))
      (node (ref "C3") (pin "1") (pinfunction "1_1") (pintype "passive"))
      (node (ref "C4") (pin "1") (pinfunction "1_1") (pintype "passive"))
      (node (ref "C5") (pin "1") (pinfunction "1_1") (pintype "passive"))
      (node (ref "C6") (pin "1") (pinfunction "1_1") (pintype "passive"))
      (node (ref "C7") (pin "1") (pinfunction "1_1") (pintype "passive"))
      (node (ref "C8") (pin "2") (pinfunction "2_2") (pintype "passive"))
      (node (ref "C9") (pin "1") (pinfunction "1_1") (pintype "passive"))
      (node (ref "LCD1") (pin "36") (pinfunction "GND_36") (pintype "passive"))
      (node (ref "LCD1") (pin "4") (pinfunction "GLED_4") (pintype "passive"))
      (node (ref "LCD1") (pin "5") (pinfunction "GLED_5") (pintype "passive"))
      (node (ref "P1") (pin "4") (pinfunction "4_4") (pintype "passive"))
      (node (ref "P10") (pin "10") (pintype "passive"))
      (node (ref "P10") (pin "11") (pintype "passive"))
      (node (ref "P10") (pin "8") (pintype "passive"))
      (node (ref "P12") (pin "10") (pinfunction "10_10") (pintype "passive"))
      (node (ref "P12") (pin "11") (pinfunction "11_11") (pintype "passive"))
      (node (ref "P12") (pin "12") (pinfunction "12_12") (pintype "passive"))
      (node (ref "P12") (pin "13") (pinfunction "13_13") (pintype "passive"))
      (node (ref "P12") (pin "14") (pinfunction "14_14") (pintype "passive"))
      (node (ref "P12") (pin "9") (pinfunction "9_9") (pintype "passive"))
      (node (ref "P13") (pin "5") (pinfunction "5_5") (pintype "passive"))
      (node (ref "P13") (pin "6") (pinfunction "6_6") (pintype "passive"))
      (node (ref "P2") (pin "0") (pinfunction "GND_0") (pintype "power_in"))
      (node (ref "P2") (pin "4") (pinfunction "GND_4") (pintype "power_in"))
      (node (ref "P4") (pin "0") (pinfunction "GND_0") (pintype "power_in"))
      (node (ref "P4") (pin "4") (pinfunction "GND_4") (pintype "power_in"))
      (node (ref "P9") (pin "27") (pinfunction "27_27") (pintype "passive"))
      (node (ref "P9") (pin "28") (pinfunction "28_28") (pintype "passive"))
      (node (ref "R10") (pin "1") (pintype "passive"))
      (node (ref "R7") (pin "1") (pintype "passive"))
      (node (ref "R9") (pin "2") (pintype "passive"))
      (node (ref "S3") (pin "1") (pinfunction "1_1") (pintype "passive"))
      (node (ref "U1") (pin "2") (pinfunction "GND_2") (pintype "power_in"))
      (node (ref "U2") (pin "10") (pinfunction "VSS_10") (pintype "power_in"))
      (node (ref "U2") (pin "19") (pinfunction "VSSA_19") (pintype "power_in"))
      (node (ref "U2") (pin "20") (pinfunction "VREF-_20") (pintype "power_in"))
      (node (ref "U2") (pin "27") (pinfunction "VSS_27") (pintype "power_in"))
      (node (ref "U2") (pin "41") (pinfunction "VSS_41") (pintype "power_in"))
      (node (ref "U2") (pin "47") (pinfunction "VSS_47") (pintype "power_in"))
      (node (ref "U2") (pin "99") (pinfunction "VSS_99") (pintype "power_in"))
    )
    (net (code "105") (name "Net-(C26-Pad2)") (class "Default")
      (node (ref "C26") (pin "2") (pinfunction "2_2") (pintype "passive"))
      (node (ref "P10") (pin "5") (pintype "passive"))
    )
    (net (code "106") (name "Net-(C27-Pad2)") (class "Default")
      (node (ref "C27") (pin "2") (pinfunction "2_2") (pintype "passive"))
      (node (ref "P10") (pin "4") (pintype "passive"))
    )
    (net (code "107") (name "Net-(D1-A)") (class "Default")
      (node (ref "D1") (pin "1") (pinfunction "A_1") (pintype "passive"))
      (node (ref "R1") (pin "2") (pintype "passive"))
    )
    (net (code "108") (name "Net-(D2-A)") (class "Default")
      (node (ref "D2") (pin "1") (pinfunction "A_1") (pintype "passive"))
      (node (ref "R4") (pin "2") (pintype "passive"))
    )
    (net (code "109") (name "Net-(D3-K)") (class "Default")
      (node (ref "D3") (pin "2") (pinfunction "K_2") (pintype "passive"))
      (node (ref "R9") (pin "1") (pintype "passive"))
    )
    (net (code "110") (name "Net-(P10-Pad9)") (class "Default")
      (node (ref "P10") (pin "9") (pintype "passive"))
      (node (ref "R21") (pin "2") (pintype "passive"))
    )
    (net (code "111") (name "Net-(P10-Pad12)") (class "Default")
      (node (ref "P10") (pin "12") (pintype "passive"))
      (node (ref "R22") (pin "2") (pintype "passive"))
    )
    (net (code "112") (name "Net-(R7-Pad2)") (class "Default")
      (node (ref "R7") (pin "2") (pintype "passive"))
      (node (ref "S2") (pin "2") (pinfunction "2_2") (pintype "passive"))
    )
    (net (code "113") (name "Net-(S1-COMMON)") (class "Default")
      (node (ref "F1") (pin "2") (pinfunction "2_2") (pintype "passive"))
      (node (ref "S1") (pin "1") (pinfunction "COMMON_1") (pintype "passive"))
    )
    (net (code "114") (name "Net-(U1-SW)") (class "Default")
      (node (ref "L1") (pin "1") (pinfunction "1_1") (pintype "passive"))
      (node (ref "U1") (pin "3") (pinfunction "SW_3") (pintype "output"))
    )
    (net (code "115") (name "VBUS") (class "Default")
      (node (ref "C11") (pin "1") (pinfunction "1_1") (pintype "passive"))
      (node (ref "C18") (pin "1") (pinfunction "1_1") (pintype "passive"))
      (node (ref "F1") (pin "1") (pinfunction "1_1") (pintype "passive"))
      (node (ref "P13") (pin "9") (pinfunction "9_9") (pintype "passive"))
      (node (ref "P2") (pin "1") (pinfunction "+5V_1") (pintype "power_in"))
      (node (ref "P4") (pin "1") (pinfunction "+5V_1") (pintype "power_in"))
      (node (ref "P8") (pin "5") (pinfunction "5_5") (pintype "passive"))
      (node (ref "P8") (pin "6") (pinfunction "6_6") (pintype "passive"))
      (node (ref "P8") (pin "7") (pinfunction "7_7") (pintype "passive"))
      (node (ref "P8") (pin "8") (pinfunction "8_8") (pintype "passive"))
    )
    (net (code "116") (name "VDD") (class "Default")
      (node (ref "C13") (pin "1") (pinfunction "1_1") (pintype "passive"))
      (node (ref "C19") (pin "2") (pinfunction "2_2") (pintype "passive"))
      (node (ref "C22") (pin "2") (pinfunction "2_2") (pintype "passive"))
      (node (ref "C23") (pin "2") (pinfunction "2_2") (pintype "passive"))
      (node (ref "C6") (pin "2") (pinfunction "2_2") (pintype "passive"))
      (node (ref "C8") (pin "1") (pinfunction "1_1") (pintype "passive"))
      (node (ref "D4") (pin "2") (pinfunction "K_2") (pintype "passive"))
      (node (ref "P13") (pin "7") (pinfunction "7_7") (pintype "passive"))
      (node (ref "P13") (pin "8") (pinfunction "8_8") (pintype "passive"))
      (node (ref "R1") (pin "1") (pintype "passive"))
      (node (ref "R2") (pin "1") (pintype "passive"))
      (node (ref "R23") (pin "1") (pintype "passive"))
      (node (ref "R4") (pin "1") (pintype "passive"))
      (node (ref "R6") (pin "2") (pinfunction "2_2") (pintype "passive"))
      (node (ref "U2") (pin "100") (pinfunction "VDD_100") (pintype "power_in"))
      (node (ref "U2") (pin "11") (pinfunction "VDD_11") (pintype "power_in"))
      (node (ref "U2") (pin "28") (pinfunction "VDD_28") (pintype "power_in"))
      (node (ref "U2") (pin "46") (pinfunction "VDD_46") (pintype "power_in"))
      (node (ref "U2") (pin "75") (pinfunction "VDD_75") (pintype "power_in"))
    )
    (net (code "117") (name "unconnected-(P10-Pad7)") (class "Default")
      (node (ref "P10") (pin "7") (pintype "passive"))
    )
    (net (code "118") (name "unconnected-(S1-NO-Pad3)") (class "Default")
      (node (ref "S1") (pin "3") (pinfunction "NO_3") (pintype "passive"))
    )
    (net (code "119") (name "unconnected-(U1-NC.-Pad1)") (class "Default")
      (node (ref "U1") (pin "1") (pinfunction "NC._1") (pintype "passive"))
    )
  )
)
